# MAIN.net
KiCad netlist of a schematic drawn in Altium Designer
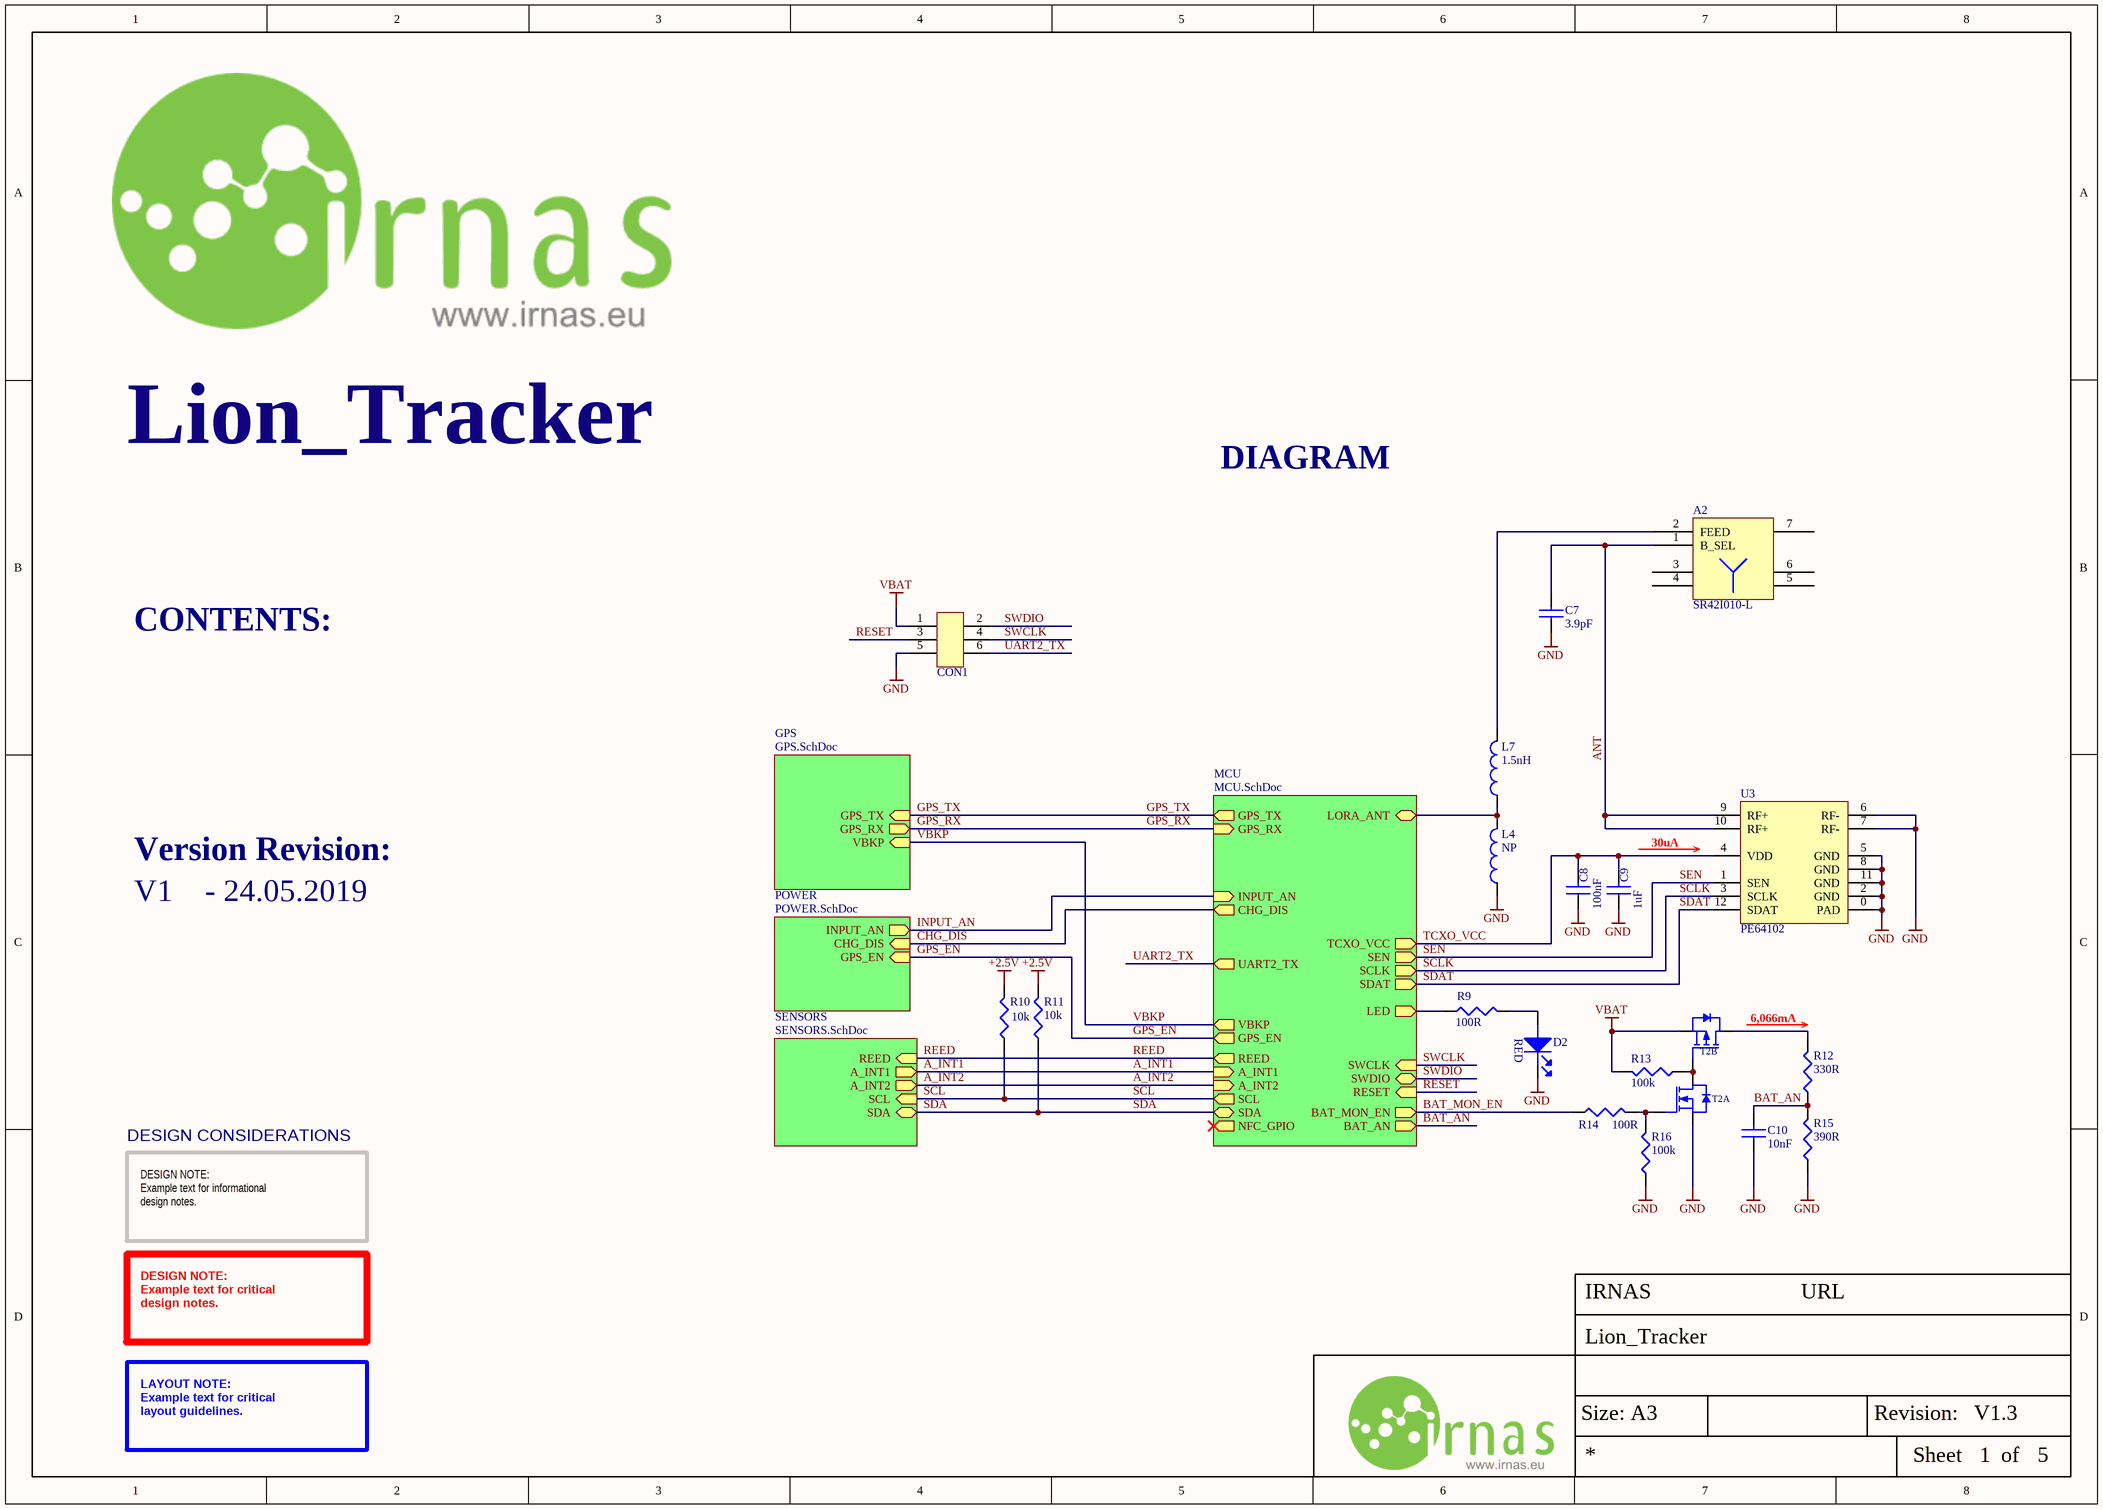
[diagram p0: MAIN.SchDoc]

(export (version "E")
  (design (tool "Eeschema 10.0.6"))
  (components
    (comp (ref "A2")
      (value "SR42I010-L")
      (footprint "SR42I010-L")
      (description "Antenna SMD -4dBi Gain 870MHz/928MHz Automotive 7-Pin SMD T/R")
      (fields (field (name "MANUFACTURER") "Antenova") (field (name "MANUFACTURER PART NUMBER") "SR42I010-R"))
      (libsource (lib "Passive") (part "ANT - SR42I010-L"))
    )
    (comp (ref "C7")
      (value "3.9pF")
      (footprint "CAP0402")
      (description "3.9 pF, 50 V, 0402 [1005 Metric], ± 0.25pF, NP0")
      (fields
        (field (name "MANUFACTURER") "KEMET")
        (field (name "MANUFACTURER PART NUMBER") "MC0402N3R9C500CT")
      )
      (libsource (lib "Passive") (part "C - 3.9pF/0402"))
    )
    (comp (ref "C8")
      (value "100nF")
      (footprint "CAP0402")
      (description "0.1 F, 16 V,  5%, X5R, MC Series")
      (fields
        (field (name "MANUFACTURER") "Multicomp")
        (field (name "MANUFACTURER PART NUMBER") "MC0402X104J160CT")
      )
      (libsource (lib "Passive") (part "C - 100nF/0402"))
    )
    (comp (ref "C9")
      (value "1uF")
      (footprint "CAP0402")
      (description "CAP CER 1UF 10V 20% X5R 0402")
      (fields
        (field (name "MANUFACTURER") "Murata")
        (field (name "MANUFACTURER PART NUMBER") "GRM155R61A105ME15D")
      )
      (libsource (lib "Passive") (part "C - 1uF/0402"))
    )
    (comp (ref "C10")
      (value "10nF")
      (footprint "CAP0402")
      (description "CAP CER 10000PF 16V X7R 0402")
      (fields
        (field (name "MANUFACTURER") "Murata")
        (field (name "MANUFACTURER PART NUMBER") "GRM155R71C103KA01D")
      )
      (libsource (lib "Passive") (part "C - 10nF/0402"))
    )
    (comp (ref "CON1")
      (value "Tag connect")
      (footprint "TC2030-IDC-NL")
      (libsource (lib "Connectors") (part "tag connecot 6 pin"))
    )
    (comp (ref "D2")
      (value "LED RED")
      (footprint "LED0603")
      (description "BROADCOM LIMITED - HSMS-C190 - LED, RED, 10MCD, 626NM")
      (fields
        (field (name "MANUFACTURER") "BROADCOM LIMITED")
        (field (name "MANUFACTURER PART NUMBER") "HSMS-C190")
      )
      (libsource (lib "Active") (part "LED - LED RED"))
    )
    (comp (ref "L4")
      (value "NP")
      (footprint "IND0402")
      (description "Inductor RF Chip Multi-Layer 4.3nH 0.3nH 100MHz 8Q-Factor Air 300mA 210mOhm DCR 0402 Paper T/R")
      (fields
        (field (name "MANUFACTURER") "Murata")
        (field (name "MANUFACTURER PART NUMBER") "LQG15HN4N3S02D")
      )
      (libsource (lib "Passive") (part "L - 4.3nH/0402"))
    )
    (comp (ref "L7")
      (value "1.5nH")
      (footprint "IND0402")
      (description "1.5 nH, LQG15HS_02 Series, 1 A, 0402")
      (fields
        (field (name "MANUFACTURER") "Murata")
        (field (name "MANUFACTURER PART NUMBER") "LQG15HS1N5S02D")
      )
      (libsource (lib "Passive") (part "L - 1.5nH/0402"))
    )
    (comp (ref "R9")
      (value "100R")
      (footprint "RES0402")
      (description "100 ohm, 50 V, 0402 [1005 Metric], 62.5 mW,  1%")
      (fields
        (field (name "MANUFACTURER") "Multicomp")
        (field (name "MANUFACTURER PART NUMBER") "MCMR04X1000FTL")
      )
      (libsource (lib "Passive") (part "R - 100R/0402"))
    )
    (comp (ref "R10")
      (value "10k")
      (footprint "RES0402")
      (description "10 kohm, 50 V, 0402 [1005 Metric], 62.5 mW,  1%, MCWR Series")
      (fields
        (field (name "MANUFACTURER") "Multicomp")
        (field (name "MANUFACTURER PART NUMBER") "MCWR04X1002FTL")
      )
      (libsource (lib "Passive") (part "R - 10k/0402"))
    )
    (comp (ref "R11")
      (value "10k")
      (footprint "RES0402")
      (description "10 kohm, 50 V, 0402 [1005 Metric], 62.5 mW,  1%, MCWR Series")
      (fields
        (field (name "MANUFACTURER") "Multicomp")
        (field (name "MANUFACTURER PART NUMBER") "MCWR04X1002FTL")
      )
      (libsource (lib "Passive") (part "R - 10k/0402"))
    )
    (comp (ref "R12")
      (value "330R")
      (footprint "RES0402")
      (fields
        (field (name "MANUFACTURER") "Multicomp")
        (field (name "MANUFACTURER PART NUMBER") "MCMR04X3300FTL")
        (field (name "TOLERANCE") "1%")
      )
      (libsource (lib "Passive") (part "R - 330R/0402"))
    )
    (comp (ref "R13")
      (value "100k")
      (footprint "RES0402")
      (description "100KOHM, 1%, 0.0625W")
      (fields
        (field (name "MANUFACTURER") "Multicomp")
        (field (name "MANUFACTURER PART NUMBER") "MCWR04X1003FTL")
      )
      (libsource (lib "Passive") (part "R - 100k/0402"))
    )
    (comp (ref "R14")
      (value "100R")
      (footprint "RES0402")
      (description "100 ohm, 50 V, 0402 [1005 Metric], 62.5 mW,  1%")
      (fields
        (field (name "MANUFACTURER") "Multicomp")
        (field (name "MANUFACTURER PART NUMBER") "MCMR04X1000FTL")
      )
      (libsource (lib "Passive") (part "R - 100R/0402"))
    )
    (comp (ref "R15")
      (value "390R")
      (footprint "RES0402")
      (description "390 ohm, MCWR Series, 50 V, Thick Film, 62.5 mW")
      (fields (field (name "MANUFACTURER") "Multicomp") (field (name "MANUFACTURER PART NUMBER") "390/0402"))
      (libsource (lib "Passive") (part "R - 390R/0402"))
    )
    (comp (ref "R16")
      (value "100k")
      (footprint "RES0402")
      (description "100KOHM, 1%, 0.0625W")
      (fields
        (field (name "MANUFACTURER") "Multicomp")
        (field (name "MANUFACTURER PART NUMBER") "MCWR04X1003FTL")
      )
      (libsource (lib "Passive") (part "R - 100k/0402"))
    )
    (comp (ref "T2")
      (value "VT6M1T2CR")
      (footprint "VMT6")
      (description "Dual MOSFET, N and P Channel, 100 mA, 20 V, 2.5 ohm, 4.5 V, 1 V")
      (fields (field (name "AUTHOR") "Ciril Golob"))
      (libsource (lib "Active") (part "T_M - VT6M1T2CR"))
    )
    (comp (ref "U3")
      (value "PE64102")
      (footprint "QFN-12")
      (description "RF IC Digitally Tunable Capacitor General Purpose 100MHz ~ 3GHz SPI Interface 12-QFN (2x2)")
      (fields (field (name "MANUFACTURER") "u-blox") (field (name "MANUFACTURER PART NUMBER") "MAX-M8Q-0"))
      (libsource (lib "Active") (part "RF - PE64102"))
    )
  )
  (nets
    (net (code "1") (name "+2.5V") (class "Default")
      (node (ref "R10") (pin "2") (pinfunction "2_2") (pintype "passive"))
      (node (ref "R11") (pin "2") (pinfunction "2_2") (pintype "passive"))
    )
    (net (code "2") (name "/ANT") (class "Default")
      (node (ref "A2") (pin "1") (pinfunction "B_SEL_1") (pintype "passive"))
      (node (ref "C7") (pin "2") (pinfunction "2_2") (pintype "passive"))
      (node (ref "U3") (pin "10") (pinfunction "RF+_10") (pintype "passive"))
      (node (ref "U3") (pin "9") (pinfunction "RF+_9") (pintype "passive"))
    )
    (net (code "5") (name "/BAT_AN") (class "Default")
      (node (ref "C10") (pin "2") (pinfunction "2_2") (pintype "passive"))
      (node (ref "R12") (pin "1") (pinfunction "1_1") (pintype "passive"))
      (node (ref "R15") (pin "2") (pinfunction "2_2") (pintype "passive"))
    )
    (net (code "6") (name "/BAT_MON_EN") (class "Default")
      (node (ref "R14") (pin "1") (pinfunction "1_1") (pintype "passive"))
    )
    (net (code "12") (name "/LED") (class "Default")
      (node (ref "R9") (pin "1") (pinfunction "1_1") (pintype "passive"))
    )
    (net (code "13") (name "/LORA_ANT") (class "Default")
      (node (ref "L4") (pin "2") (pinfunction "2_2") (pintype "passive"))
      (node (ref "L7") (pin "1") (pinfunction "1_1") (pintype "passive"))
    )
    (net (code "16") (name "/RESET") (class "Default")
      (node (ref "CON1") (pin "3") (pinfunction "3_3") (pintype "open_collector"))
    )
    (net (code "17") (name "/SCL") (class "Default")
      (node (ref "R10") (pin "1") (pinfunction "1_1") (pintype "passive"))
    )
    (net (code "18") (name "/SCLK") (class "Default")
      (node (ref "U3") (pin "3") (pinfunction "SCLK_3") (pintype "passive"))
    )
    (net (code "19") (name "/SDA") (class "Default")
      (node (ref "R11") (pin "1") (pinfunction "1_1") (pintype "passive"))
    )
    (net (code "20") (name "/SDAT") (class "Default")
      (node (ref "U3") (pin "12") (pinfunction "SDAT_12") (pintype "passive"))
    )
    (net (code "21") (name "/SEN") (class "Default")
      (node (ref "U3") (pin "1") (pinfunction "SEN_1") (pintype "passive"))
    )
    (net (code "22") (name "/SWCLK") (class "Default")
      (node (ref "CON1") (pin "4") (pinfunction "4_4") (pintype "open_collector"))
    )
    (net (code "23") (name "/SWDIO") (class "Default")
      (node (ref "CON1") (pin "2") (pinfunction "2_2") (pintype "open_collector"))
    )
    (net (code "24") (name "/TCXO_VCC") (class "Default")
      (node (ref "C8") (pin "2") (pinfunction "2_2") (pintype "passive"))
      (node (ref "C9") (pin "2") (pinfunction "2_2") (pintype "passive"))
      (node (ref "U3") (pin "4") (pinfunction "VDD_4") (pintype "passive"))
    )
    (net (code "25") (name "/UART2_TX") (class "Default")
      (node (ref "CON1") (pin "6") (pinfunction "6_6") (pintype "passive"))
    )
    (net (code "27") (name "GND") (class "Default")
      (node (ref "C10") (pin "1") (pinfunction "1_1") (pintype "passive"))
      (node (ref "C7") (pin "1") (pinfunction "1_1") (pintype "passive"))
      (node (ref "C8") (pin "1") (pinfunction "1_1") (pintype "passive"))
      (node (ref "C9") (pin "1") (pinfunction "1_1") (pintype "passive"))
      (node (ref "CON1") (pin "5") (pinfunction "5_5") (pintype "open_collector"))
      (node (ref "D2") (pin "1") (pinfunction "cathode_1") (pintype "passive"))
      (node (ref "L4") (pin "1") (pinfunction "1_1") (pintype "passive"))
      (node (ref "R15") (pin "1") (pinfunction "1_1") (pintype "passive"))
      (node (ref "R16") (pin "1") (pinfunction "1_1") (pintype "passive"))
      (node (ref "T2") (pin "1") (pinfunction "S1_1") (pintype "passive"))
      (node (ref "U3") (pin "0") (pinfunction "PAD_0") (pintype "passive"))
      (node (ref "U3") (pin "11") (pinfunction "GND_11") (pintype "passive"))
      (node (ref "U3") (pin "2") (pinfunction "GND_2") (pintype "passive"))
      (node (ref "U3") (pin "5") (pinfunction "GND_5") (pintype "passive"))
      (node (ref "U3") (pin "6") (pinfunction "RF-_6") (pintype "passive"))
      (node (ref "U3") (pin "7") (pinfunction "RF-_7") (pintype "passive"))
      (node (ref "U3") (pin "8") (pinfunction "GND_8") (pintype "passive"))
    )
    (net (code "28") (name "Net-(A2-FEED)") (class "Default")
      (node (ref "A2") (pin "2") (pinfunction "FEED_2") (pintype "passive"))
      (node (ref "L7") (pin "2") (pinfunction "2_2") (pintype "passive"))
    )
    (net (code "29") (name "Net-(D2-ANODE)") (class "Default")
      (node (ref "D2") (pin "2") (pinfunction "ANODE_2") (pintype "passive"))
      (node (ref "R9") (pin "2") (pinfunction "2_2") (pintype "passive"))
    )
    (net (code "30") (name "Net-(T2A-D1)") (class "Default")
      (node (ref "R13") (pin "1") (pinfunction "1_1") (pintype "passive"))
      (node (ref "T2") (pin "5") (pinfunction "G2_5") (pintype "passive"))
      (node (ref "T2") (pin "6") (pinfunction "D1_6") (pintype "passive"))
    )
    (net (code "31") (name "Net-(T2A-G1)") (class "Default")
      (node (ref "R14") (pin "2") (pinfunction "2_2") (pintype "passive"))
      (node (ref "R16") (pin "2") (pinfunction "2_2") (pintype "passive"))
      (node (ref "T2") (pin "2") (pinfunction "G1_2") (pintype "passive"))
    )
    (net (code "32") (name "Net-(T2B-D2)") (class "Default")
      (node (ref "R12") (pin "2") (pinfunction "2_2") (pintype "passive"))
      (node (ref "T2") (pin "3") (pinfunction "D2_3") (pintype "passive"))
    )
    (net (code "33") (name "VBAT") (class "Default")
      (node (ref "CON1") (pin "1") (pinfunction "1_1") (pintype "open_collector"))
      (node (ref "R13") (pin "2") (pinfunction "2_2") (pintype "passive"))
      (node (ref "T2") (pin "4") (pinfunction "S2_4") (pintype "passive"))
    )
    (net (code "34") (name "unconnected-(A2-Pad3)") (class "Default")
      (node (ref "A2") (pin "3") (pintype "passive"))
    )
    (net (code "35") (name "unconnected-(A2-Pad4)") (class "Default")
      (node (ref "A2") (pin "4") (pintype "passive"))
    )
    (net (code "36") (name "unconnected-(A2-Pad5)") (class "Default")
      (node (ref "A2") (pin "5") (pintype "passive"))
    )
    (net (code "37") (name "unconnected-(A2-Pad6)") (class "Default")
      (node (ref "A2") (pin "6") (pintype "passive"))
    )
    (net (code "38") (name "unconnected-(A2-Pad7)") (class "Default")
      (node (ref "A2") (pin "7") (pintype "passive"))
    )
  )
)
